# microdevel_power.net
KiCad netlist of a schematic drawn in Altium Designer
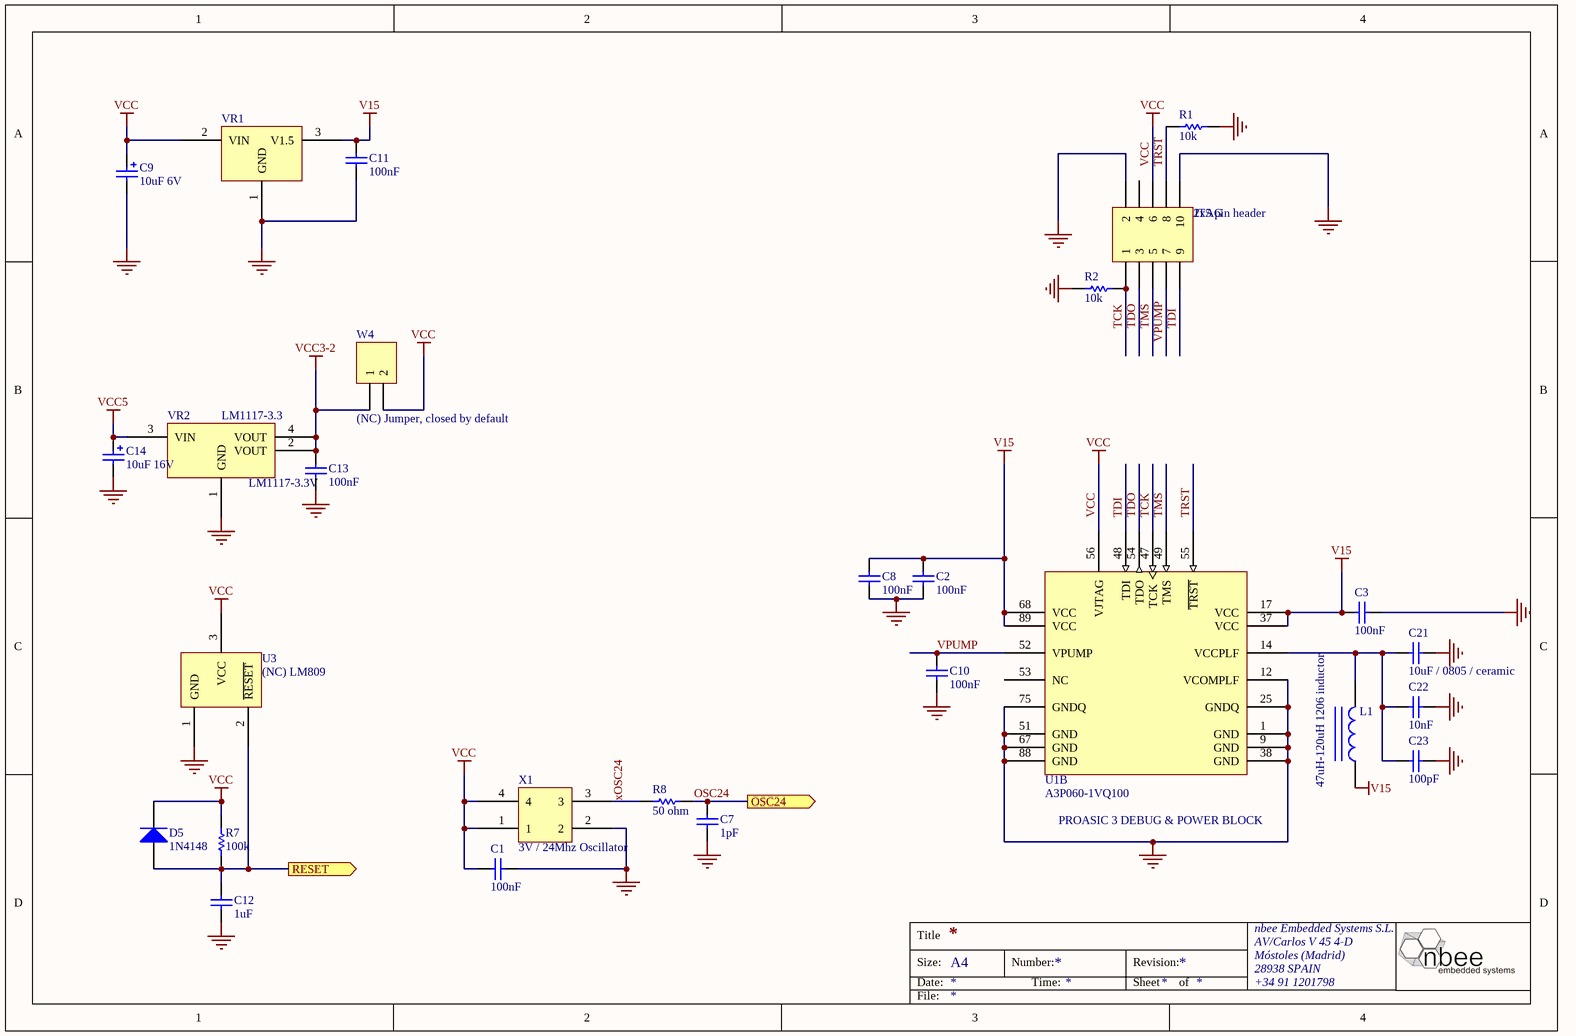
[diagram p0: microdevel_power.schdoc]

(export (version "E")
  (design (tool "Eeschema 10.0.6"))
  (components
    (comp (ref "C1")
      (value "100nF")
      (footprint "0603")
      (description "Capacitor (Semiconductor SIM Model)")
      (fields (field (name "PUBLISHER") "Altium Limited"))
      (libsource (lib "Miscellaneous Devices") (part "Cap Semi"))
    )
    (comp (ref "C2")
      (value "100nF")
      (footprint "0603")
      (description "Capacitor (Semiconductor SIM Model)")
      (fields (field (name "PUBLISHER") "Altium Limited"))
      (libsource (lib "Miscellaneous Devices") (part "Cap Semi"))
    )
    (comp (ref "C3")
      (value "100nF")
      (footprint "0603")
      (description "Capacitor (Semiconductor SIM Model)")
      (fields (field (name "PUBLISHER") "Altium Limited"))
      (libsource (lib "Miscellaneous Devices") (part "Cap Semi"))
    )
    (comp (ref "C7")
      (value "1pF")
      (footprint "0603")
      (description "Capacitor (Semiconductor SIM Model)")
      (fields (field (name "PUBLISHER") "Altium Limited"))
      (libsource (lib "Miscellaneous Devices") (part "Cap Semi"))
    )
    (comp (ref "C8")
      (value "100nF")
      (footprint "0603")
      (description "Capacitor (Semiconductor SIM Model)")
      (fields (field (name "PUBLISHER") "Altium Limited"))
      (libsource (lib "Miscellaneous Devices") (part "Cap Semi"))
    )
    (comp (ref "C9")
      (value "10uF 6V")
      (footprint "CC-6030")
      (description "Polarized Capacitor (Surface Mount)")
      (fields
        (field (name "MANUFACTURER") "Generic Components")
        (field (name "PUBLISHER") "Altium Hobart Technology Centre")
      )
      (libsource (lib "Miscellaneous Devices") (part "Cap Pol3"))
    )
    (comp (ref "C10")
      (value "100nF")
      (footprint "0603")
      (description "Capacitor (Semiconductor SIM Model)")
      (fields (field (name "PUBLISHER") "Altium Limited"))
      (libsource (lib "Miscellaneous Devices") (part "Cap Semi"))
    )
    (comp (ref "C11")
      (value "100nF")
      (footprint "0603")
      (description "Capacitor (Semiconductor SIM Model)")
      (fields (field (name "PUBLISHER") "Altium Limited"))
      (libsource (lib "Miscellaneous Devices") (part "Cap Semi"))
    )
    (comp (ref "C12")
      (value "1uF")
      (footprint "0603")
      (description "Capacitor (Semiconductor SIM Model)")
      (fields (field (name "PUBLISHER") "Altium Limited"))
      (libsource (lib "Miscellaneous Devices") (part "Cap Semi"))
    )
    (comp (ref "C13")
      (value "100nF")
      (footprint "0603")
      (description "Capacitor (Semiconductor SIM Model)")
      (fields (field (name "PUBLISHER") "Altium Limited"))
      (libsource (lib "Miscellaneous Devices") (part "Cap Semi"))
    )
    (comp (ref "C14")
      (value "10uF 16V")
      (footprint "CC-6030")
      (description "Polarized Capacitor (Surface Mount)")
      (fields
        (field (name "MANUFACTURER") "Generic Components")
        (field (name "PUBLISHER") "Altium Hobart Technology Centre")
      )
      (libsource (lib "Miscellaneous Devices") (part "Cap Pol3"))
    )
    (comp (ref "C21")
      (value "10uF / 0805 / ceramic")
      (footprint "0805")
      (description "10uF ceramic capacitor")
      (fields (field (name "PUBLISHER") "Altium Limited"))
      (libsource (lib "Miscellaneous Devices") (part "Cap Semi"))
    )
    (comp (ref "C22")
      (value "10nF")
      (footprint "0603")
      (description "Capacitor (Semiconductor SIM Model)")
      (fields (field (name "PUBLISHER") "Altium Limited"))
      (libsource (lib "Miscellaneous Devices") (part "Cap Semi"))
    )
    (comp (ref "C23")
      (value "100pF")
      (footprint "0603")
      (description "Capacitor (Semiconductor SIM Model)")
      (fields (field (name "PUBLISHER") "Altium Limited"))
      (libsource (lib "Miscellaneous Devices") (part "Cap Semi"))
    )
    (comp (ref "D5")
      (value "1N4148")
      (footprint "DIODE_1206")
      (description "Default Diode")
      (fields (field (name "PUBLISHER") "Altium Limited"))
      (libsource (lib "Miscellaneous Devices") (part "Diode"))
    )
    (comp (ref "JTAG")
      (value "2x5 pin header")
      (footprint "HDR2X5")
      (description "Header, 5-Pin, Dual row")
      (fields (field (name "PUBLISHER") "Altium Limited"))
      (libsource (lib "Miscellaneous Connectors") (part "Header 5X2"))
    )
    (comp (ref "L1")
      (value "47uH-120uH 1206 inductor")
      (footprint "1206")
      (description "Magnetic-Core Inductor")
      (fields (field (name "PUBLISHER") "Altium Limited"))
      (libsource (lib "Miscellaneous Devices") (part "Inductor Iron"))
    )
    (comp (ref "R1")
      (value "10k")
      (footprint "0603")
      (description "Resistor")
      (fields (field (name "PUBLISHER") "Altium Limited"))
      (libsource (lib "Miscellaneous Devices") (part "Res1"))
    )
    (comp (ref "R2")
      (value "10k")
      (footprint "0603")
      (description "Resistor")
      (fields (field (name "PUBLISHER") "Altium Limited"))
      (libsource (lib "Miscellaneous Devices") (part "Res1"))
    )
    (comp (ref "R7")
      (value "100k")
      (footprint "0603")
      (description "Resistor")
      (fields (field (name "PUBLISHER") "Altium Limited"))
      (libsource (lib "Miscellaneous Devices") (part "Res1"))
    )
    (comp (ref "R8")
      (value "50 ohm")
      (footprint "0603")
      (description "Resistor")
      (fields (field (name "PUBLISHER") "Altium Limited"))
      (libsource (lib "Miscellaneous Devices") (part "Res1"))
    )
    (comp (ref "U1")
      (value "A3P060-1VQ100")
      (footprint "A3P060")
      (fields (field (name "PUBLISHER") "Altium Limited"))
      (libsource (lib "Actel ProASIC3") (part "A3P060-1VQ100"))
    )
    (comp (ref "U3") (value "(NC) LM809") (footprint "SOT23-2") (libsource (lib "Schlib1") (part "LM809")))
    (comp (ref "VR1") (value "LDO 1.5V") (footprint "G4TOB") (libsource (lib "Schlib1") (part "VREG1_5")))
    (comp (ref "VR2")
      (value "LM1117-3.3V")
      (footprint "DSO-G3")
      (fields (field (name "ALTIUM_VALUE") "LM1117-3.3"))
      (libsource (lib "libreria") (part "LM1117-3.3"))
    )
    (comp (ref "W4")
      (value "(NC) Jumper, closed by default")
      (footprint "JUMPER")
      (description "Header, 2-Pin, Right Angle")
      (fields (field (name "PUBLISHER") "Altium Limited"))
      (libsource (lib "Miscellaneous Connectors") (part "Header 2H"))
    )
    (comp (ref "X1")
      (value "3V / 24Mhz Oscillator")
      (footprint "OSC 3x5mm")
      (libsource (lib "Schlib1") (part "OSCILATOR"))
    )
  )
  (nets
    (net (code "1") (name "/OSC24") (class "Default")
      (node (ref "C7") (pin "2") (pinfunction "2_2") (pintype "passive"))
      (node (ref "R8") (pin "1") (pinfunction "1_1") (pintype "passive"))
    )
    (net (code "2") (name "/RESET") (class "Default")
      (node (ref "C12") (pin "2") (pinfunction "2_2") (pintype "passive"))
      (node (ref "D5") (pin "1") (pinfunction "A_1") (pintype "passive"))
      (node (ref "R7") (pin "1") (pinfunction "1_1") (pintype "passive"))
      (node (ref "U3") (pin "2") (pinfunction "~{RESET}_2") (pintype "passive"))
    )
    (net (code "3") (name "/TCK") (class "Default")
      (node (ref "JTAG") (pin "1") (pinfunction "1_1") (pintype "passive"))
      (node (ref "R2") (pin "2") (pinfunction "2_2") (pintype "passive"))
      (node (ref "U1") (pin "47") (pinfunction "TCK_47") (pintype "input"))
    )
    (net (code "4") (name "/TDI") (class "Default")
      (node (ref "JTAG") (pin "9") (pinfunction "9_9") (pintype "passive"))
      (node (ref "U1") (pin "48") (pinfunction "TDI_48") (pintype "input"))
    )
    (net (code "5") (name "/TDO") (class "Default")
      (node (ref "JTAG") (pin "3") (pinfunction "3_3") (pintype "passive"))
      (node (ref "U1") (pin "54") (pinfunction "TDO_54") (pintype "output"))
    )
    (net (code "6") (name "/TMS") (class "Default")
      (node (ref "JTAG") (pin "5") (pinfunction "5_5") (pintype "passive"))
      (node (ref "U1") (pin "49") (pinfunction "TMS_49") (pintype "input"))
    )
    (net (code "7") (name "/TRST") (class "Default")
      (node (ref "JTAG") (pin "8") (pinfunction "8_8") (pintype "passive"))
      (node (ref "R1") (pin "2") (pinfunction "2_2") (pintype "passive"))
      (node (ref "U1") (pin "55") (pinfunction "~{TRST}_55") (pintype "input"))
    )
    (net (code "8") (name "/VPUMP") (class "Default")
      (node (ref "C10") (pin "2") (pinfunction "2_2") (pintype "passive"))
      (node (ref "JTAG") (pin "7") (pinfunction "7_7") (pintype "passive"))
      (node (ref "U1") (pin "52") (pinfunction "VPUMP_52") (pintype "power_in"))
    )
    (net (code "9") (name "/xOSC24") (class "Default")
      (node (ref "R8") (pin "2") (pinfunction "2_2") (pintype "passive"))
      (node (ref "X1") (pin "3") (pinfunction "3_3") (pintype "passive"))
    )
    (net (code "10") (name "GND") (class "Default")
      (node (ref "C1") (pin "2") (pinfunction "2_2") (pintype "passive"))
      (node (ref "C10") (pin "1") (pinfunction "1_1") (pintype "passive"))
      (node (ref "C11") (pin "1") (pinfunction "1_1") (pintype "passive"))
      (node (ref "C12") (pin "1") (pinfunction "1_1") (pintype "passive"))
      (node (ref "C13") (pin "1") (pinfunction "1_1") (pintype "passive"))
      (node (ref "C14") (pin "2") (pinfunction "2_2") (pintype "passive"))
      (node (ref "C2") (pin "1") (pinfunction "1_1") (pintype "passive"))
      (node (ref "C21") (pin "2") (pinfunction "2_2") (pintype "passive"))
      (node (ref "C22") (pin "2") (pinfunction "2_2") (pintype "passive"))
      (node (ref "C23") (pin "2") (pinfunction "2_2") (pintype "passive"))
      (node (ref "C3") (pin "2") (pinfunction "2_2") (pintype "passive"))
      (node (ref "C7") (pin "1") (pinfunction "1_1") (pintype "passive"))
      (node (ref "C8") (pin "1") (pinfunction "1_1") (pintype "passive"))
      (node (ref "C9") (pin "2") (pinfunction "2_2") (pintype "passive"))
      (node (ref "JTAG") (pin "10") (pinfunction "10_10") (pintype "passive"))
      (node (ref "JTAG") (pin "2") (pinfunction "2_2") (pintype "passive"))
      (node (ref "R1") (pin "1") (pinfunction "1_1") (pintype "passive"))
      (node (ref "R2") (pin "1") (pinfunction "1_1") (pintype "passive"))
      (node (ref "U1") (pin "1") (pinfunction "GND_1") (pintype "power_in"))
      (node (ref "U1") (pin "12") (pinfunction "VCOMPLF_12") (pintype "power_in"))
      (node (ref "U1") (pin "25") (pinfunction "GNDQ_25") (pintype "power_in"))
      (node (ref "U1") (pin "38") (pinfunction "GND_38") (pintype "power_in"))
      (node (ref "U1") (pin "51") (pinfunction "GND_51") (pintype "power_in"))
      (node (ref "U1") (pin "67") (pinfunction "GND_67") (pintype "power_in"))
      (node (ref "U1") (pin "75") (pinfunction "GNDQ_75") (pintype "power_in"))
      (node (ref "U1") (pin "88") (pinfunction "GND_88") (pintype "power_in"))
      (node (ref "U1") (pin "9") (pinfunction "GND_9") (pintype "power_in"))
      (node (ref "U3") (pin "1") (pinfunction "GND_1") (pintype "passive"))
      (node (ref "VR1") (pin "1") (pinfunction "GND_1") (pintype "power_in"))
      (node (ref "VR2") (pin "1") (pinfunction "GND_1") (pintype "passive"))
      (node (ref "X1") (pin "2") (pinfunction "2_2") (pintype "passive"))
    )
    (net (code "11") (name "Net-(U1B-VCCPLF)") (class "Default")
      (node (ref "C21") (pin "1") (pinfunction "1_1") (pintype "passive"))
      (node (ref "C22") (pin "1") (pinfunction "1_1") (pintype "passive"))
      (node (ref "C23") (pin "1") (pinfunction "1_1") (pintype "passive"))
      (node (ref "L1") (pin "2") (pinfunction "2_2") (pintype "passive"))
      (node (ref "U1") (pin "14") (pinfunction "VCCPLF_14") (pintype "power_in"))
    )
    (net (code "12") (name "V15") (class "Default")
      (node (ref "C11") (pin "2") (pinfunction "2_2") (pintype "passive"))
      (node (ref "C2") (pin "2") (pinfunction "2_2") (pintype "passive"))
      (node (ref "C3") (pin "1") (pinfunction "1_1") (pintype "passive"))
      (node (ref "C8") (pin "2") (pinfunction "2_2") (pintype "passive"))
      (node (ref "L1") (pin "1") (pinfunction "1_1") (pintype "passive"))
      (node (ref "U1") (pin "17") (pinfunction "VCC_17") (pintype "power_in"))
      (node (ref "U1") (pin "37") (pinfunction "VCC_37") (pintype "power_in"))
      (node (ref "U1") (pin "68") (pinfunction "VCC_68") (pintype "power_in"))
      (node (ref "U1") (pin "89") (pinfunction "VCC_89") (pintype "power_in"))
      (node (ref "VR1") (pin "3") (pinfunction "V1.5_3") (pintype "power_in"))
    )
    (net (code "13") (name "VCC") (class "Default")
      (node (ref "C1") (pin "1") (pinfunction "1_1") (pintype "passive"))
      (node (ref "C9") (pin "1") (pinfunction "1_1") (pintype "passive"))
      (node (ref "D5") (pin "2") (pinfunction "K_2") (pintype "passive"))
      (node (ref "JTAG") (pin "6") (pinfunction "6_6") (pintype "passive"))
      (node (ref "R7") (pin "2") (pinfunction "2_2") (pintype "passive"))
      (node (ref "U1") (pin "56") (pinfunction "VJTAG_56") (pintype "power_in"))
      (node (ref "U3") (pin "3") (pinfunction "VCC_3") (pintype "passive"))
      (node (ref "VR1") (pin "2") (pinfunction "VIN_2") (pintype "power_in"))
      (node (ref "W4") (pin "2") (pinfunction "2_2") (pintype "passive"))
      (node (ref "X1") (pin "1") (pinfunction "1_1") (pintype "passive"))
      (node (ref "X1") (pin "4") (pinfunction "4_4") (pintype "passive"))
    )
    (net (code "14") (name "VCC3-2") (class "Default")
      (node (ref "C13") (pin "2") (pinfunction "2_2") (pintype "passive"))
      (node (ref "VR2") (pin "2") (pinfunction "VOUT_2") (pintype "passive"))
      (node (ref "VR2") (pin "4") (pinfunction "VOUT_4") (pintype "passive"))
      (node (ref "W4") (pin "1") (pinfunction "1_1") (pintype "passive"))
    )
    (net (code "15") (name "VCC5") (class "Default")
      (node (ref "C14") (pin "1") (pinfunction "1_1") (pintype "passive"))
      (node (ref "VR2") (pin "3") (pinfunction "VIN_3") (pintype "passive"))
    )
    (net (code "16") (name "unconnected-(JTAG-Pad4)") (class "Default")
      (node (ref "JTAG") (pin "4") (pinfunction "4_4") (pintype "passive"))
    )
    (net (code "17") (name "unconnected-(U1B-NC-Pad53)") (class "Default")
      (node (ref "U1") (pin "53") (pinfunction "NC_53") (pintype "passive"))
    )
  )
)
